# Digital_Port_L_State_LED_Inducator.net
KiCad netlist of a schematic drawn in Altium Designer
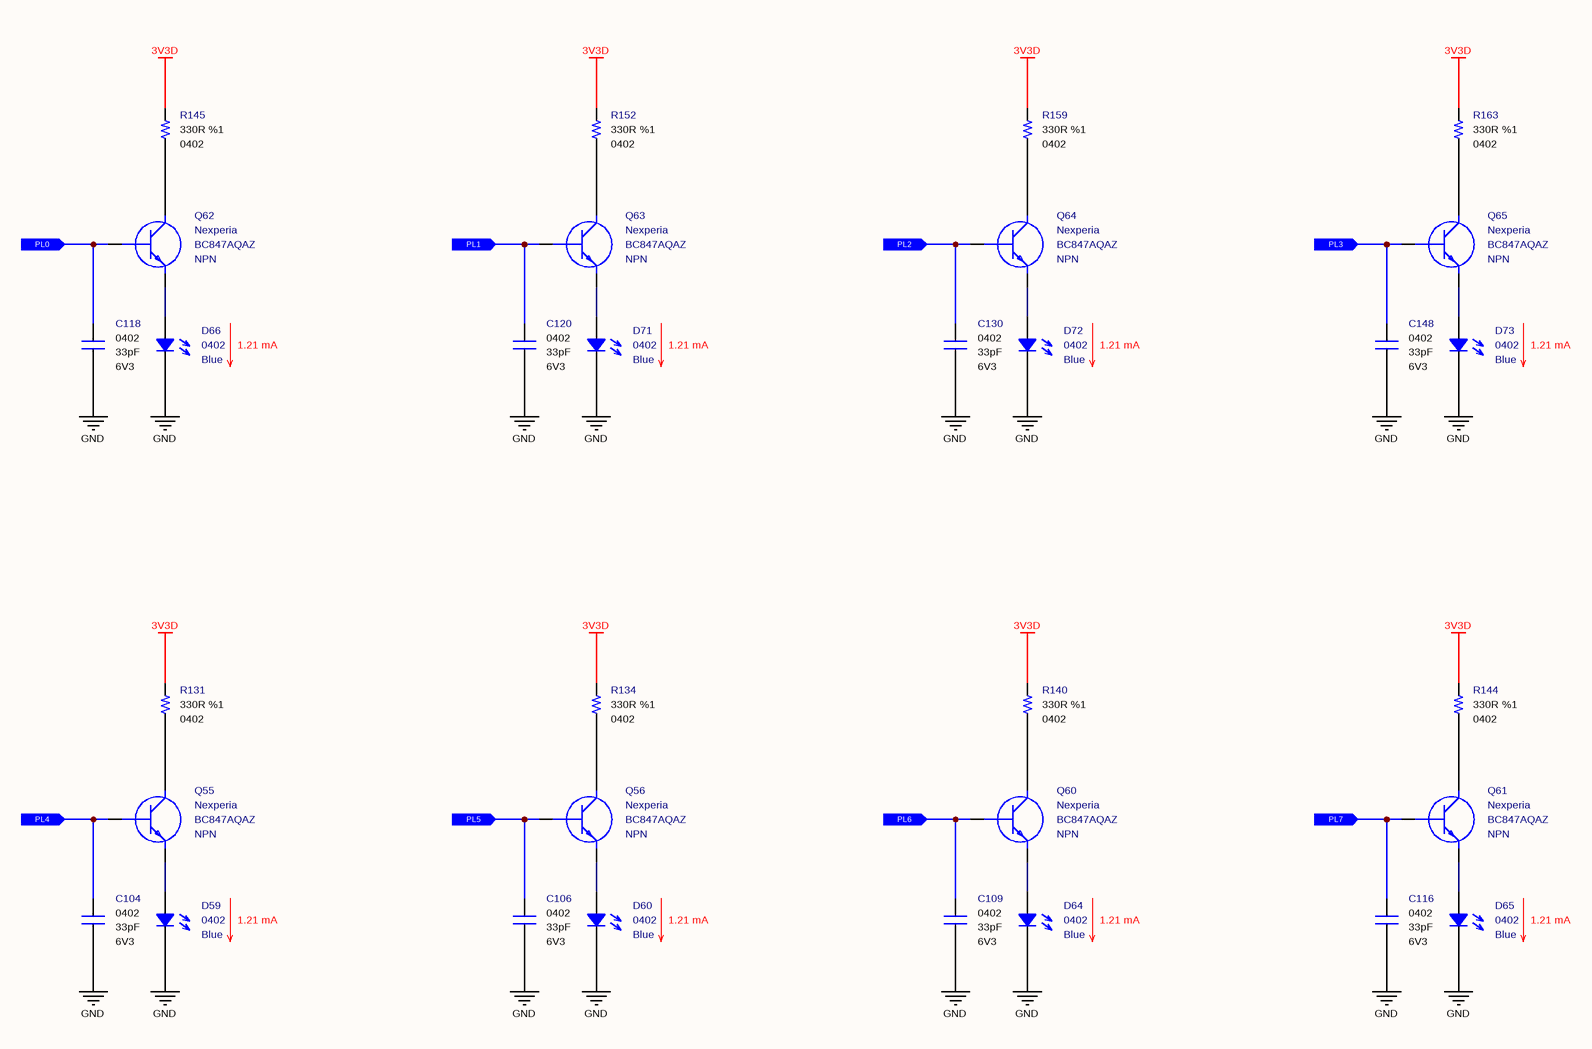
[diagram p0: Digital Port L State LED Inducator.SchDoc]

(export (version "E")
  (design (tool "Eeschema 10.0.6"))
  (components
    (comp (ref "C104")
      (value "33pF")
      (footprint "CAPACITOR_0402")
      (description "Capacitor - 33pF [0402] (Ceramic)")
      (fields
        (field (name "CASE") "0402")
        (field (name "TOLERANCE") "10%")
        (field (name "VOLTAGE") "6V3")
        (field (name "MANUFACTURER PART NUMBER") "C0402C330J9RACAUTO")
      )
      (libsource (lib "Ovoo_Library") (part "Capacitor - 33pF [0402-6V3]"))
    )
    (comp (ref "C106")
      (value "33pF")
      (footprint "CAPACITOR_0402")
      (description "Capacitor - 33pF [0402] (Ceramic)")
      (fields
        (field (name "CASE") "0402")
        (field (name "TOLERANCE") "10%")
        (field (name "VOLTAGE") "6V3")
        (field (name "MANUFACTURER PART NUMBER") "C0402C330J9RACAUTO")
      )
      (libsource (lib "Ovoo_Library") (part "Capacitor - 33pF [0402-6V3]"))
    )
    (comp (ref "C109")
      (value "33pF")
      (footprint "CAPACITOR_0402")
      (description "Capacitor - 33pF [0402] (Ceramic)")
      (fields
        (field (name "CASE") "0402")
        (field (name "TOLERANCE") "10%")
        (field (name "VOLTAGE") "6V3")
        (field (name "MANUFACTURER PART NUMBER") "C0402C330J9RACAUTO")
      )
      (libsource (lib "Ovoo_Library") (part "Capacitor - 33pF [0402-6V3]"))
    )
    (comp (ref "C116")
      (value "33pF")
      (footprint "CAPACITOR_0402")
      (description "Capacitor - 33pF [0402] (Ceramic)")
      (fields
        (field (name "CASE") "0402")
        (field (name "TOLERANCE") "10%")
        (field (name "VOLTAGE") "6V3")
        (field (name "MANUFACTURER PART NUMBER") "C0402C330J9RACAUTO")
      )
      (libsource (lib "Ovoo_Library") (part "Capacitor - 33pF [0402-6V3]"))
    )
    (comp (ref "C118")
      (value "33pF")
      (footprint "CAPACITOR_0402")
      (description "Capacitor - 33pF [0402] (Ceramic)")
      (fields
        (field (name "CASE") "0402")
        (field (name "TOLERANCE") "10%")
        (field (name "VOLTAGE") "6V3")
        (field (name "MANUFACTURER PART NUMBER") "C0402C330J9RACAUTO")
      )
      (libsource (lib "Ovoo_Library") (part "Capacitor - 33pF [0402-6V3]"))
    )
    (comp (ref "C120")
      (value "33pF")
      (footprint "CAPACITOR_0402")
      (description "Capacitor - 33pF [0402] (Ceramic)")
      (fields
        (field (name "CASE") "0402")
        (field (name "TOLERANCE") "10%")
        (field (name "VOLTAGE") "6V3")
        (field (name "MANUFACTURER PART NUMBER") "C0402C330J9RACAUTO")
      )
      (libsource (lib "Ovoo_Library") (part "Capacitor - 33pF [0402-6V3]"))
    )
    (comp (ref "C130")
      (value "33pF")
      (footprint "CAPACITOR_0402")
      (description "Capacitor - 33pF [0402] (Ceramic)")
      (fields
        (field (name "CASE") "0402")
        (field (name "TOLERANCE") "10%")
        (field (name "VOLTAGE") "6V3")
        (field (name "MANUFACTURER PART NUMBER") "C0402C330J9RACAUTO")
      )
      (libsource (lib "Ovoo_Library") (part "Capacitor - 33pF [0402-6V3]"))
    )
    (comp (ref "C148")
      (value "33pF")
      (footprint "CAPACITOR_0402")
      (description "Capacitor - 33pF [0402] (Ceramic)")
      (fields
        (field (name "CASE") "0402")
        (field (name "TOLERANCE") "10%")
        (field (name "VOLTAGE") "6V3")
        (field (name "MANUFACTURER PART NUMBER") "C0402C330J9RACAUTO")
      )
      (libsource (lib "Ovoo_Library") (part "Capacitor - 33pF [0402-6V3]"))
    )
    (comp (ref "D59")
      (value "SMD LED (Blue)")
      (footprint "LED_0402")
      (description "Standard LEDs - SMD PICOLEDTM;BLUE LED; 25M @ 5MA")
      (fields
        (field (name "MANUFACTURER_PART_NUMBER") "SMLP13BC8TT86")
        (field (name "MOUSER_PART_NUMBER") "755-SMLP13BC8TT86")
        (field (name "CASE") "0402")
        (field (name "COLOR") "Blue")
      )
      (libsource (lib "Ovoo_Library") (part "Diode - LED (0402-Blue)"))
    )
    (comp (ref "D60")
      (value "SMD LED (Blue)")
      (footprint "LED_0402")
      (description "Standard LEDs - SMD PICOLEDTM;BLUE LED; 25M @ 5MA")
      (fields
        (field (name "MANUFACTURER_PART_NUMBER") "SMLP13BC8TT86")
        (field (name "MOUSER_PART_NUMBER") "755-SMLP13BC8TT86")
        (field (name "CASE") "0402")
        (field (name "COLOR") "Blue")
      )
      (libsource (lib "Ovoo_Library") (part "Diode - LED (0402-Blue)"))
    )
    (comp (ref "D64")
      (value "SMD LED (Blue)")
      (footprint "LED_0402")
      (description "Standard LEDs - SMD PICOLEDTM;BLUE LED; 25M @ 5MA")
      (fields
        (field (name "MANUFACTURER_PART_NUMBER") "SMLP13BC8TT86")
        (field (name "MOUSER_PART_NUMBER") "755-SMLP13BC8TT86")
        (field (name "CASE") "0402")
        (field (name "COLOR") "Blue")
      )
      (libsource (lib "Ovoo_Library") (part "Diode - LED (0402-Blue)"))
    )
    (comp (ref "D65")
      (value "SMD LED (Blue)")
      (footprint "LED_0402")
      (description "Standard LEDs - SMD PICOLEDTM;BLUE LED; 25M @ 5MA")
      (fields
        (field (name "MANUFACTURER_PART_NUMBER") "SMLP13BC8TT86")
        (field (name "MOUSER_PART_NUMBER") "755-SMLP13BC8TT86")
        (field (name "CASE") "0402")
        (field (name "COLOR") "Blue")
      )
      (libsource (lib "Ovoo_Library") (part "Diode - LED (0402-Blue)"))
    )
    (comp (ref "D66")
      (value "SMD LED (Blue)")
      (footprint "LED_0402")
      (description "Standard LEDs - SMD PICOLEDTM;BLUE LED; 25M @ 5MA")
      (fields
        (field (name "MANUFACTURER_PART_NUMBER") "SMLP13BC8TT86")
        (field (name "MOUSER_PART_NUMBER") "755-SMLP13BC8TT86")
        (field (name "CASE") "0402")
        (field (name "COLOR") "Blue")
      )
      (libsource (lib "Ovoo_Library") (part "Diode - LED (0402-Blue)"))
    )
    (comp (ref "D71")
      (value "SMD LED (Blue)")
      (footprint "LED_0402")
      (description "Standard LEDs - SMD PICOLEDTM;BLUE LED; 25M @ 5MA")
      (fields
        (field (name "MANUFACTURER_PART_NUMBER") "SMLP13BC8TT86")
        (field (name "MOUSER_PART_NUMBER") "755-SMLP13BC8TT86")
        (field (name "CASE") "0402")
        (field (name "COLOR") "Blue")
      )
      (libsource (lib "Ovoo_Library") (part "Diode - LED (0402-Blue)"))
    )
    (comp (ref "D72")
      (value "SMD LED (Blue)")
      (footprint "LED_0402")
      (description "Standard LEDs - SMD PICOLEDTM;BLUE LED; 25M @ 5MA")
      (fields
        (field (name "MANUFACTURER_PART_NUMBER") "SMLP13BC8TT86")
        (field (name "MOUSER_PART_NUMBER") "755-SMLP13BC8TT86")
        (field (name "CASE") "0402")
        (field (name "COLOR") "Blue")
      )
      (libsource (lib "Ovoo_Library") (part "Diode - LED (0402-Blue)"))
    )
    (comp (ref "D73")
      (value "SMD LED (Blue)")
      (footprint "LED_0402")
      (description "Standard LEDs - SMD PICOLEDTM;BLUE LED; 25M @ 5MA")
      (fields
        (field (name "MANUFACTURER_PART_NUMBER") "SMLP13BC8TT86")
        (field (name "MOUSER_PART_NUMBER") "755-SMLP13BC8TT86")
        (field (name "CASE") "0402")
        (field (name "COLOR") "Blue")
      )
      (libsource (lib "Ovoo_Library") (part "Diode - LED (0402-Blue)"))
    )
    (comp (ref "Q55")
      (value "Bipolar NPN Transistors")
      (footprint "SOT1215")
      (description "Bipolar Transistors - BJT BC847AQA/DFN1010D-3/REEL 7\" Q2")
      (fields
        (field (name "MOUSER_PART_NUMBER") "771-BC847AQAZ")
        (field (name "MANUFACTURER_NAME") "Nexperia")
        (field (name "MANUFACTURER_PART_NUMBER") "BC847AQAZ")
        (field (name "POLARITY") "NPN")
      )
      (libsource (lib "Ovoo_Library") (part "Transistor - BC847"))
    )
    (comp (ref "Q56")
      (value "Bipolar NPN Transistors")
      (footprint "SOT1215")
      (description "Bipolar Transistors - BJT BC847AQA/DFN1010D-3/REEL 7\" Q2")
      (fields
        (field (name "MOUSER_PART_NUMBER") "771-BC847AQAZ")
        (field (name "MANUFACTURER_NAME") "Nexperia")
        (field (name "MANUFACTURER_PART_NUMBER") "BC847AQAZ")
        (field (name "POLARITY") "NPN")
      )
      (libsource (lib "Ovoo_Library") (part "Transistor - BC847"))
    )
    (comp (ref "Q60")
      (value "Bipolar NPN Transistors")
      (footprint "SOT1215")
      (description "Bipolar Transistors - BJT BC847AQA/DFN1010D-3/REEL 7\" Q2")
      (fields
        (field (name "MOUSER_PART_NUMBER") "771-BC847AQAZ")
        (field (name "MANUFACTURER_NAME") "Nexperia")
        (field (name "MANUFACTURER_PART_NUMBER") "BC847AQAZ")
        (field (name "POLARITY") "NPN")
      )
      (libsource (lib "Ovoo_Library") (part "Transistor - BC847"))
    )
    (comp (ref "Q61")
      (value "Bipolar NPN Transistors")
      (footprint "SOT1215")
      (description "Bipolar Transistors - BJT BC847AQA/DFN1010D-3/REEL 7\" Q2")
      (fields
        (field (name "MOUSER_PART_NUMBER") "771-BC847AQAZ")
        (field (name "MANUFACTURER_NAME") "Nexperia")
        (field (name "MANUFACTURER_PART_NUMBER") "BC847AQAZ")
        (field (name "POLARITY") "NPN")
      )
      (libsource (lib "Ovoo_Library") (part "Transistor - BC847"))
    )
    (comp (ref "Q62")
      (value "Bipolar NPN Transistors")
      (footprint "SOT1215")
      (description "Bipolar Transistors - BJT BC847AQA/DFN1010D-3/REEL 7\" Q2")
      (fields
        (field (name "MOUSER_PART_NUMBER") "771-BC847AQAZ")
        (field (name "MANUFACTURER_NAME") "Nexperia")
        (field (name "MANUFACTURER_PART_NUMBER") "BC847AQAZ")
        (field (name "POLARITY") "NPN")
      )
      (libsource (lib "Ovoo_Library") (part "Transistor - BC847"))
    )
    (comp (ref "Q63")
      (value "Bipolar NPN Transistors")
      (footprint "SOT1215")
      (description "Bipolar Transistors - BJT BC847AQA/DFN1010D-3/REEL 7\" Q2")
      (fields
        (field (name "MOUSER_PART_NUMBER") "771-BC847AQAZ")
        (field (name "MANUFACTURER_NAME") "Nexperia")
        (field (name "MANUFACTURER_PART_NUMBER") "BC847AQAZ")
        (field (name "POLARITY") "NPN")
      )
      (libsource (lib "Ovoo_Library") (part "Transistor - BC847"))
    )
    (comp (ref "Q64")
      (value "Bipolar NPN Transistors")
      (footprint "SOT1215")
      (description "Bipolar Transistors - BJT BC847AQA/DFN1010D-3/REEL 7\" Q2")
      (fields
        (field (name "MOUSER_PART_NUMBER") "771-BC847AQAZ")
        (field (name "MANUFACTURER_NAME") "Nexperia")
        (field (name "MANUFACTURER_PART_NUMBER") "BC847AQAZ")
        (field (name "POLARITY") "NPN")
      )
      (libsource (lib "Ovoo_Library") (part "Transistor - BC847"))
    )
    (comp (ref "Q65")
      (value "Bipolar NPN Transistors")
      (footprint "SOT1215")
      (description "Bipolar Transistors - BJT BC847AQA/DFN1010D-3/REEL 7\" Q2")
      (fields
        (field (name "MOUSER_PART_NUMBER") "771-BC847AQAZ")
        (field (name "MANUFACTURER_NAME") "Nexperia")
        (field (name "MANUFACTURER_PART_NUMBER") "BC847AQAZ")
        (field (name "POLARITY") "NPN")
      )
      (libsource (lib "Ovoo_Library") (part "Transistor - BC847"))
    )
    (comp (ref "R131")
      (value "330R")
      (footprint "RESISTOR_0402")
      (description "Thick Film Resistors - SMD 1/16 W 330 Ohm 1%")
      (fields
        (field (name "TOLERANCE") "%1")
        (field (name "CASE") "0402")
        (field (name "MANUFACTURER PART NUMBER") "CRCW0402330RFKED")
        (field (name "MOUSER PART NUMBER") "71-CRCW0402-330-E3")
      )
      (libsource (lib "Ovoo_Library") (part "Resistor - 330R"))
    )
    (comp (ref "R134")
      (value "330R")
      (footprint "RESISTOR_0402")
      (description "Thick Film Resistors - SMD 1/16 W 330 Ohm 1%")
      (fields
        (field (name "TOLERANCE") "%1")
        (field (name "CASE") "0402")
        (field (name "MANUFACTURER PART NUMBER") "CRCW0402330RFKED")
        (field (name "MOUSER PART NUMBER") "71-CRCW0402-330-E3")
      )
      (libsource (lib "Ovoo_Library") (part "Resistor - 330R"))
    )
    (comp (ref "R140")
      (value "330R")
      (footprint "RESISTOR_0402")
      (description "Thick Film Resistors - SMD 1/16 W 330 Ohm 1%")
      (fields
        (field (name "TOLERANCE") "%1")
        (field (name "CASE") "0402")
        (field (name "MANUFACTURER PART NUMBER") "CRCW0402330RFKED")
        (field (name "MOUSER PART NUMBER") "71-CRCW0402-330-E3")
      )
      (libsource (lib "Ovoo_Library") (part "Resistor - 330R"))
    )
    (comp (ref "R144")
      (value "330R")
      (footprint "RESISTOR_0402")
      (description "Thick Film Resistors - SMD 1/16 W 330 Ohm 1%")
      (fields
        (field (name "TOLERANCE") "%1")
        (field (name "CASE") "0402")
        (field (name "MANUFACTURER PART NUMBER") "CRCW0402330RFKED")
        (field (name "MOUSER PART NUMBER") "71-CRCW0402-330-E3")
      )
      (libsource (lib "Ovoo_Library") (part "Resistor - 330R"))
    )
    (comp (ref "R145")
      (value "330R")
      (footprint "RESISTOR_0402")
      (description "Thick Film Resistors - SMD 1/16 W 330 Ohm 1%")
      (fields
        (field (name "TOLERANCE") "%1")
        (field (name "CASE") "0402")
        (field (name "MANUFACTURER PART NUMBER") "CRCW0402330RFKED")
        (field (name "MOUSER PART NUMBER") "71-CRCW0402-330-E3")
      )
      (libsource (lib "Ovoo_Library") (part "Resistor - 330R"))
    )
    (comp (ref "R152")
      (value "330R")
      (footprint "RESISTOR_0402")
      (description "Thick Film Resistors - SMD 1/16 W 330 Ohm 1%")
      (fields
        (field (name "TOLERANCE") "%1")
        (field (name "CASE") "0402")
        (field (name "MANUFACTURER PART NUMBER") "CRCW0402330RFKED")
        (field (name "MOUSER PART NUMBER") "71-CRCW0402-330-E3")
      )
      (libsource (lib "Ovoo_Library") (part "Resistor - 330R"))
    )
    (comp (ref "R159")
      (value "330R")
      (footprint "RESISTOR_0402")
      (description "Thick Film Resistors - SMD 1/16 W 330 Ohm 1%")
      (fields
        (field (name "TOLERANCE") "%1")
        (field (name "CASE") "0402")
        (field (name "MANUFACTURER PART NUMBER") "CRCW0402330RFKED")
        (field (name "MOUSER PART NUMBER") "71-CRCW0402-330-E3")
      )
      (libsource (lib "Ovoo_Library") (part "Resistor - 330R"))
    )
    (comp (ref "R163")
      (value "330R")
      (footprint "RESISTOR_0402")
      (description "Thick Film Resistors - SMD 1/16 W 330 Ohm 1%")
      (fields
        (field (name "TOLERANCE") "%1")
        (field (name "CASE") "0402")
        (field (name "MANUFACTURER PART NUMBER") "CRCW0402330RFKED")
        (field (name "MOUSER PART NUMBER") "71-CRCW0402-330-E3")
      )
      (libsource (lib "Ovoo_Library") (part "Resistor - 330R"))
    )
  )
  (nets
    (net (code "1") (name "/PL0") (class "Default")
      (node (ref "C118") (pin "1") (pinfunction "1_1") (pintype "passive"))
      (node (ref "Q62") (pin "1") (pinfunction "B_1") (pintype "passive"))
    )
    (net (code "2") (name "/PL1") (class "Default")
      (node (ref "C120") (pin "1") (pinfunction "1_1") (pintype "passive"))
      (node (ref "Q63") (pin "1") (pinfunction "B_1") (pintype "passive"))
    )
    (net (code "3") (name "/PL2") (class "Default")
      (node (ref "C130") (pin "1") (pinfunction "1_1") (pintype "passive"))
      (node (ref "Q64") (pin "1") (pinfunction "B_1") (pintype "passive"))
    )
    (net (code "4") (name "/PL3") (class "Default")
      (node (ref "C148") (pin "1") (pinfunction "1_1") (pintype "passive"))
      (node (ref "Q65") (pin "1") (pinfunction "B_1") (pintype "passive"))
    )
    (net (code "5") (name "/PL4") (class "Default")
      (node (ref "C104") (pin "1") (pinfunction "1_1") (pintype "passive"))
      (node (ref "Q55") (pin "1") (pinfunction "B_1") (pintype "passive"))
    )
    (net (code "6") (name "/PL5") (class "Default")
      (node (ref "C106") (pin "1") (pinfunction "1_1") (pintype "passive"))
      (node (ref "Q56") (pin "1") (pinfunction "B_1") (pintype "passive"))
    )
    (net (code "7") (name "/PL6") (class "Default")
      (node (ref "C109") (pin "1") (pinfunction "1_1") (pintype "passive"))
      (node (ref "Q60") (pin "1") (pinfunction "B_1") (pintype "passive"))
    )
    (net (code "8") (name "/PL7") (class "Default")
      (node (ref "C116") (pin "1") (pinfunction "1_1") (pintype "passive"))
      (node (ref "Q61") (pin "1") (pinfunction "B_1") (pintype "passive"))
    )
    (net (code "9") (name "3V3D") (class "Default")
      (node (ref "R131") (pin "2") (pinfunction "2_2") (pintype "passive"))
      (node (ref "R134") (pin "2") (pinfunction "2_2") (pintype "passive"))
      (node (ref "R140") (pin "2") (pinfunction "2_2") (pintype "passive"))
      (node (ref "R144") (pin "2") (pinfunction "2_2") (pintype "passive"))
      (node (ref "R145") (pin "2") (pinfunction "2_2") (pintype "passive"))
      (node (ref "R152") (pin "2") (pinfunction "2_2") (pintype "passive"))
      (node (ref "R159") (pin "2") (pinfunction "2_2") (pintype "passive"))
      (node (ref "R163") (pin "2") (pinfunction "2_2") (pintype "passive"))
    )
    (net (code "10") (name "GND") (class "Default")
      (node (ref "C104") (pin "2") (pinfunction "2_2") (pintype "passive"))
      (node (ref "C106") (pin "2") (pinfunction "2_2") (pintype "passive"))
      (node (ref "C109") (pin "2") (pinfunction "2_2") (pintype "passive"))
      (node (ref "C116") (pin "2") (pinfunction "2_2") (pintype "passive"))
      (node (ref "C118") (pin "2") (pinfunction "2_2") (pintype "passive"))
      (node (ref "C120") (pin "2") (pinfunction "2_2") (pintype "passive"))
      (node (ref "C130") (pin "2") (pinfunction "2_2") (pintype "passive"))
      (node (ref "C148") (pin "2") (pinfunction "2_2") (pintype "passive"))
      (node (ref "D59") (pin "1") (pinfunction "1_1") (pintype "passive"))
      (node (ref "D60") (pin "1") (pinfunction "1_1") (pintype "passive"))
      (node (ref "D64") (pin "1") (pinfunction "1_1") (pintype "passive"))
      (node (ref "D65") (pin "1") (pinfunction "1_1") (pintype "passive"))
      (node (ref "D66") (pin "1") (pinfunction "1_1") (pintype "passive"))
      (node (ref "D71") (pin "1") (pinfunction "1_1") (pintype "passive"))
      (node (ref "D72") (pin "1") (pinfunction "1_1") (pintype "passive"))
      (node (ref "D73") (pin "1") (pinfunction "1_1") (pintype "passive"))
    )
    (net (code "11") (name "Net-(Q55-C)") (class "Default")
      (node (ref "Q55") (pin "3") (pinfunction "C_3") (pintype "passive"))
      (node (ref "R131") (pin "1") (pinfunction "1_1") (pintype "passive"))
    )
    (net (code "12") (name "Net-(Q55-E)") (class "Default")
      (node (ref "D59") (pin "2") (pinfunction "2_2") (pintype "passive"))
      (node (ref "Q55") (pin "2") (pinfunction "E_2") (pintype "passive"))
    )
    (net (code "13") (name "Net-(Q56-C)") (class "Default")
      (node (ref "Q56") (pin "3") (pinfunction "C_3") (pintype "passive"))
      (node (ref "R134") (pin "1") (pinfunction "1_1") (pintype "passive"))
    )
    (net (code "14") (name "Net-(Q56-E)") (class "Default")
      (node (ref "D60") (pin "2") (pinfunction "2_2") (pintype "passive"))
      (node (ref "Q56") (pin "2") (pinfunction "E_2") (pintype "passive"))
    )
    (net (code "15") (name "Net-(Q60-C)") (class "Default")
      (node (ref "Q60") (pin "3") (pinfunction "C_3") (pintype "passive"))
      (node (ref "R140") (pin "1") (pinfunction "1_1") (pintype "passive"))
    )
    (net (code "16") (name "Net-(Q60-E)") (class "Default")
      (node (ref "D64") (pin "2") (pinfunction "2_2") (pintype "passive"))
      (node (ref "Q60") (pin "2") (pinfunction "E_2") (pintype "passive"))
    )
    (net (code "17") (name "Net-(Q61-C)") (class "Default")
      (node (ref "Q61") (pin "3") (pinfunction "C_3") (pintype "passive"))
      (node (ref "R144") (pin "1") (pinfunction "1_1") (pintype "passive"))
    )
    (net (code "18") (name "Net-(Q61-E)") (class "Default")
      (node (ref "D65") (pin "2") (pinfunction "2_2") (pintype "passive"))
      (node (ref "Q61") (pin "2") (pinfunction "E_2") (pintype "passive"))
    )
    (net (code "19") (name "Net-(Q62-C)") (class "Default")
      (node (ref "Q62") (pin "3") (pinfunction "C_3") (pintype "passive"))
      (node (ref "R145") (pin "1") (pinfunction "1_1") (pintype "passive"))
    )
    (net (code "20") (name "Net-(Q62-E)") (class "Default")
      (node (ref "D66") (pin "2") (pinfunction "2_2") (pintype "passive"))
      (node (ref "Q62") (pin "2") (pinfunction "E_2") (pintype "passive"))
    )
    (net (code "21") (name "Net-(Q63-C)") (class "Default")
      (node (ref "Q63") (pin "3") (pinfunction "C_3") (pintype "passive"))
      (node (ref "R152") (pin "1") (pinfunction "1_1") (pintype "passive"))
    )
    (net (code "22") (name "Net-(Q63-E)") (class "Default")
      (node (ref "D71") (pin "2") (pinfunction "2_2") (pintype "passive"))
      (node (ref "Q63") (pin "2") (pinfunction "E_2") (pintype "passive"))
    )
    (net (code "23") (name "Net-(Q64-C)") (class "Default")
      (node (ref "Q64") (pin "3") (pinfunction "C_3") (pintype "passive"))
      (node (ref "R159") (pin "1") (pinfunction "1_1") (pintype "passive"))
    )
    (net (code "24") (name "Net-(Q64-E)") (class "Default")
      (node (ref "D72") (pin "2") (pinfunction "2_2") (pintype "passive"))
      (node (ref "Q64") (pin "2") (pinfunction "E_2") (pintype "passive"))
    )
    (net (code "25") (name "Net-(Q65-C)") (class "Default")
      (node (ref "Q65") (pin "3") (pinfunction "C_3") (pintype "passive"))
      (node (ref "R163") (pin "1") (pinfunction "1_1") (pintype "passive"))
    )
    (net (code "26") (name "Net-(Q65-E)") (class "Default")
      (node (ref "D73") (pin "2") (pinfunction "2_2") (pintype "passive"))
      (node (ref "Q65") (pin "2") (pinfunction "E_2") (pintype "passive"))
    )
  )
)
